# Sheet1.net
KiCad netlist of a schematic drawn in Altium Designer
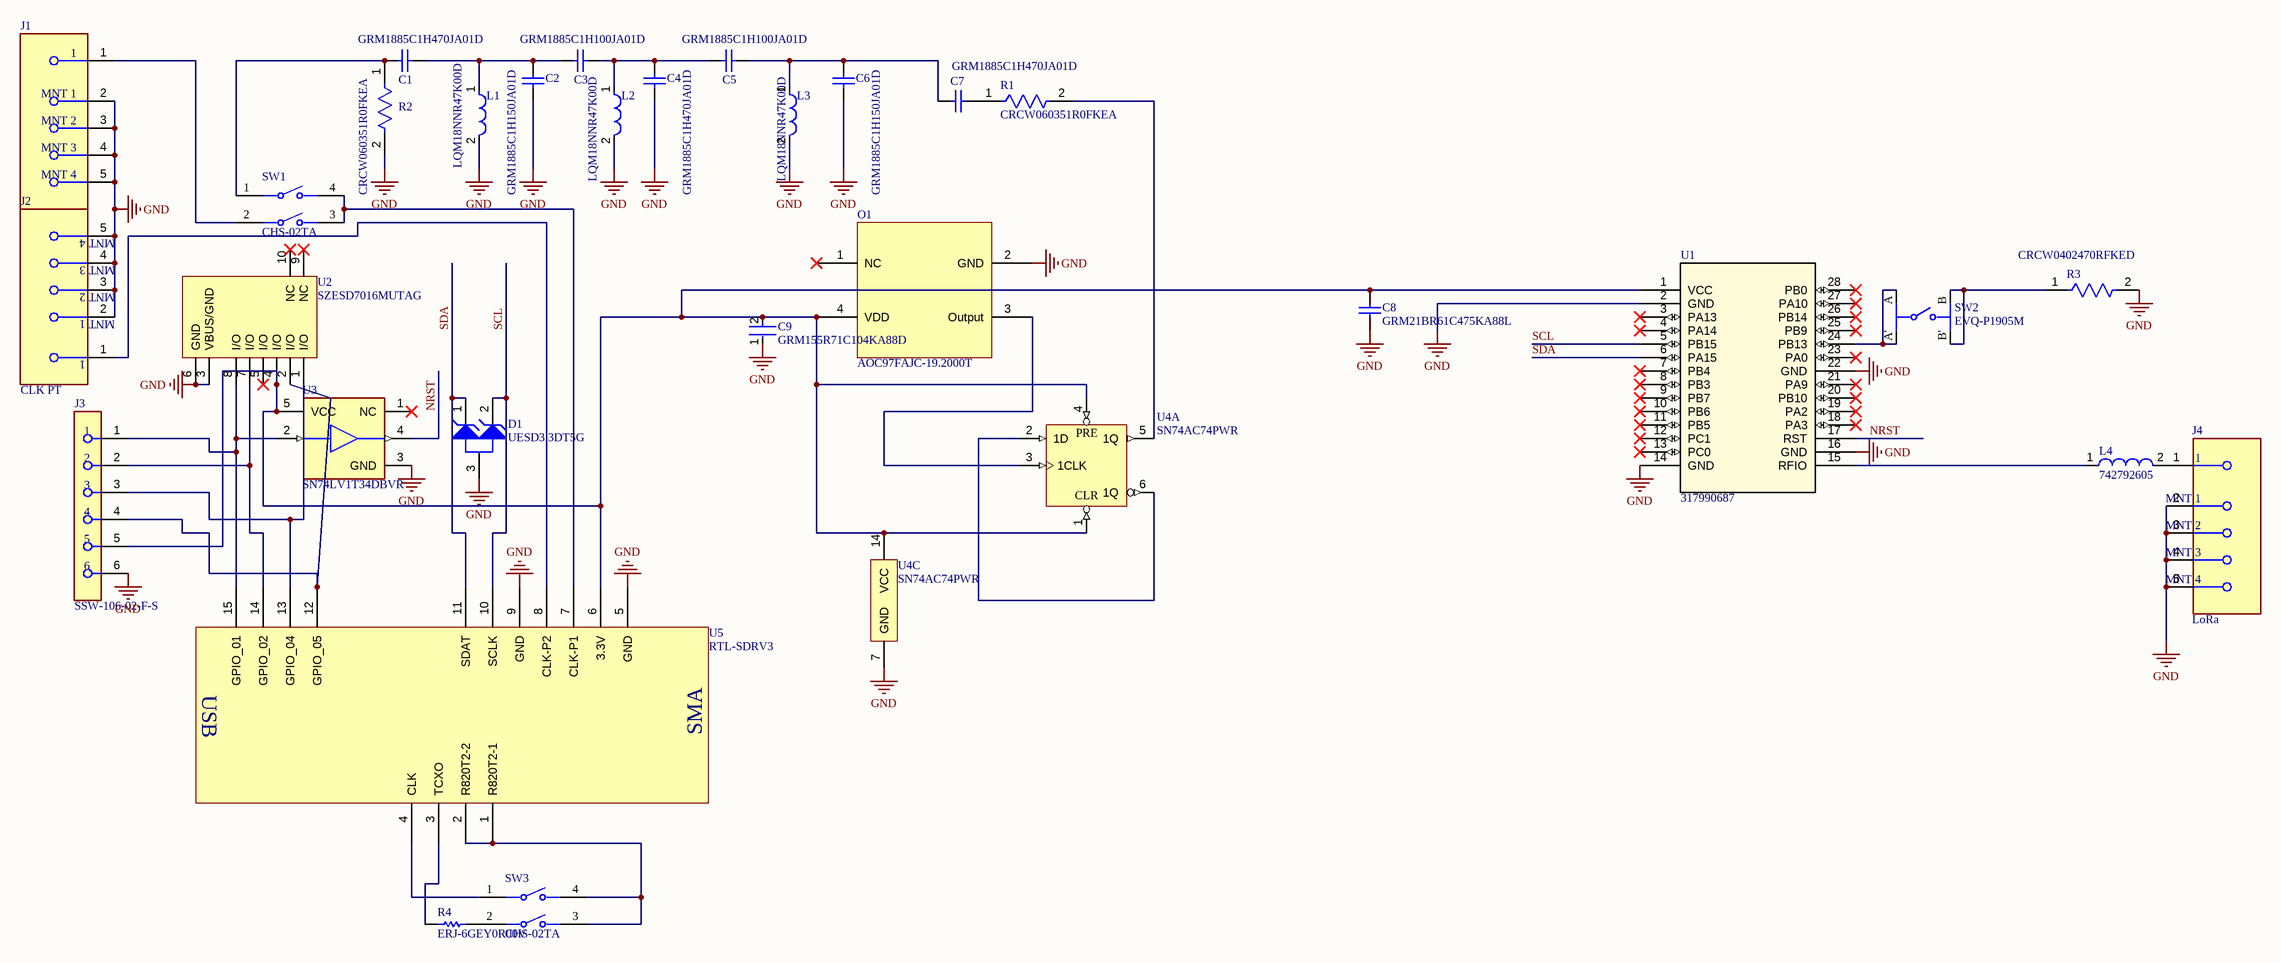
[diagram p0: Sheet1.SchDoc]

(export (version "E")
  (design (tool "Eeschema 10.0.6"))
  (components
    (comp (ref "C1")
      (value "GRM1885C1H470JA01D")
      (footprint "CAPC1608X90X35ML10T15")
      (fields (field (name "MANUFACTURER") "Murata"))
      (libsource (lib "Altium Content Vault") (part "CAP"))
    )
    (comp (ref "C2")
      (value "GRM1885C1H150JA01D")
      (footprint "CAPC1608X90X35ML10T15")
      (fields (field (name "MANUFACTURER") "Murata"))
      (libsource (lib "Altium Content Vault") (part "CAP"))
    )
    (comp (ref "C3")
      (value "GRM1885C1H100JA01D")
      (footprint "CAPC1608X90X35LL10T15")
      (fields (field (name "MANUFACTURER") "Murata"))
      (libsource (lib "Altium Content Vault") (part "CAP"))
    )
    (comp (ref "C4")
      (value "GRM1885C1H470JA01D")
      (footprint "CAPC1608X90X35ML10T15")
      (fields (field (name "MANUFACTURER") "Murata"))
      (libsource (lib "Altium Content Vault") (part "CAP"))
    )
    (comp (ref "C5")
      (value "GRM1885C1H100JA01D")
      (footprint "CAPC1608X90X35LL10T15")
      (fields (field (name "MANUFACTURER") "Murata"))
      (libsource (lib "Altium Content Vault") (part "CAP"))
    )
    (comp (ref "C6")
      (value "GRM1885C1H150JA01D")
      (footprint "CAPC1608X90X35ML10T15")
      (fields (field (name "MANUFACTURER") "Murata"))
      (libsource (lib "Altium Content Vault") (part "CAP"))
    )
    (comp (ref "C7")
      (value "GRM1885C1H470JA01D")
      (footprint "CAPC1608X90X35ML10T15")
      (fields (field (name "MANUFACTURER") "Murata"))
      (libsource (lib "Altium Content Vault") (part "CAP"))
    )
    (comp (ref "C8")
      (value "GRM21BR61C475KA88L")
      (footprint "CAPC2013X135X45LL10T25")
      (description "Chip Capacitor, 4.7 uF, +/- 10%, 16 V, -55 to 85 degC, 0805 (2012 Metric), RoHS, Tape and Reel")
      (fields (field (name "TOLERANCE") "10%"))
      (libsource (lib "Altium Content Vault") (part "CAP-NP-2"))
    )
    (comp (ref "C9")
      (value "GRM155R71C104KA88D")
      (footprint "FP-GRM15-MFG")
      (description "CAP CER 0.1UF 16V X7R 0402")
      (fields
        (field (name "TOLERANCE") "10%")
        (field (name "OCTOPART") "https://octopart.com/grm155r71c104ka88d-murata-196880")
      )
      (libsource (lib "Altium Content Vault") (part "236180d848d6139a670b325ea6854c9"))
    )
    (comp (ref "D1")
      (value "UESD3.3DT5G")
      (footprint "ONSC-SOT-723-3-631AA-01_V")
      (description "ESD Protection Diode, 3-Pin SOT-723, Pb-Free, Tape and Reel")
      (fields (field (name "MANUFACTURER") "On Semiconductor"))
      (libsource (lib "Altium Content Vault") (part "ONSC-K1K2A3-3"))
    )
    (comp (ref "J1")
      (value "CLK IO")
      (footprint "FP-73391-0083-MFG")
      (description "SMA RA JACK, PCB")
      (libsource (lib "") (part "c65b8a639cdaef1819ea20b5466f8fa_2"))
    )
    (comp (ref "J2")
      (value "CLK PT")
      (footprint "FP-73391-0083-MFG")
      (description "SMA RA JACK, PCB")
      (libsource (lib "") (part "c65b8a639cdaef1819ea20b5466f8fa_1"))
    )
    (comp (ref "J3")
      (value "SSW-106-02-F-S")
      (footprint "FP-SSW-106-02-F-S-MFG")
      (description "CONN RCPT 6POS 0.1 GOLD PCB")
      (libsource (lib "Altium Content Vault") (part "340f86754993f25901839ab6d466df7"))
    )
    (comp (ref "J4")
      (value "LoRa")
      (footprint "FP-73391-0083-MFG")
      (description "SMA RA JACK, PCB")
      (libsource (lib "Altium Content Vault") (part "c65b8a639cdaef1819ea20b5466f8fa"))
    )
    (comp (ref "L1")
      (value "LQM18NNR47K00D")
      (footprint "FP-LQM18NN_00-IPC_A")
      (description "Multilayer Type Inductor for General Circuits, 0603 (1608), 470nH, 10%, 1.35Ω, 35mA")
      (fields (field (name "TOLERANCE") "10%"))
      (libsource (lib "Altium Content Vault") (part "725321dda6339637d4d059423bc1c3c"))
    )
    (comp (ref "L2")
      (value "LQM18NNR47K00D")
      (footprint "FP-LQM18NN_00-IPC_A")
      (description "Multilayer Type Inductor for General Circuits, 0603 (1608), 470nH, 10%, 1.35Ω, 35mA")
      (fields (field (name "TOLERANCE") "10%"))
      (libsource (lib "Altium Content Vault") (part "725321dda6339637d4d059423bc1c3c"))
    )
    (comp (ref "L3")
      (value "LQM18NNR47K00D")
      (footprint "FP-LQM18NN_00-IPC_A")
      (description "Multilayer Type Inductor for General Circuits, 0603 (1608), 470nH, 10%, 1.35Ω, 35mA")
      (fields (field (name "TOLERANCE") "10%"))
      (libsource (lib "Altium Content Vault") (part "725321dda6339637d4d059423bc1c3c"))
    )
    (comp (ref "L4")
      (value "742792605")
      (footprint "SMD-0603")
      (description "SMD EMI Suppression Ferrite Bead WE-CBF, Z = 33 Ohm")
      (libsource (lib "Altium Content Vault") (part "PAS-IND-INDUCTOR-2"))
    )
    (comp (ref "O1")
      (value "AOC97FAJC-19.2000T")
      (footprint "AOC97FAJC-19.2000T")
      (libsource (lib "RTLSDRV3") (part "AOC97FAJC-19.2000T"))
    )
    (comp (ref "R1")
      (value "CRCW060351R0FKEA")
      (footprint "FP-CRCW0603-e3-MFG")
      (description "RES Thick Film, 51Ω, 1%, 0.1W, 100ppm/°C, 0603")
      (fields (field (name "TOLERANCE") "1%"))
      (libsource (lib "Altium Content Vault") (part "1029c3af85768c4190bb7ad29bc67b5"))
    )
    (comp (ref "R2")
      (value "CRCW060351R0FKEA")
      (footprint "FP-CRCW0603-e3-MFG")
      (description "RES Thick Film, 51Ω, 1%, 0.1W, 100ppm/°C, 0603")
      (fields (field (name "TOLERANCE") "1%"))
      (libsource (lib "Altium Content Vault") (part "1029c3af85768c4190bb7ad29bc67b5"))
    )
    (comp (ref "R3")
      (value "CRCW0402470RFKED")
      (footprint "FP-CRCW0402-e3-MFG")
      (description "RES Thick Film, 470Ω, 1%, 0.063W, 100ppm/°C, 0402")
      (fields (field (name "TOLERANCE") "1%"))
      (libsource (lib "Altium Content Vault") (part "1029c3af85768c4190bb7ad29bc67b5"))
    )
    (comp (ref "R4")
      (value "ERJ-6GEY0R00V")
      (footprint "RESC2013X70X40NL20T20")
      (description "Chip Resistor, 0 Ohm, +/- 1%, 0.125 W, -55 to 155 degC, 0805 (2012 Metric), RoHS, Tape and Reel")
      (fields (field (name "TOLERANCE") "5%"))
      (libsource (lib "Altium Content Vault") (part "RES-2"))
    )
    (comp (ref "SW1")
      (value "CHS-02TA")
      (footprint "FP-CHS-02TA-MFG")
      (description "SWITCH SLIDE DIP SPST 100MA 6V")
      (libsource (lib "Altium Content Vault") (part "69afdd861a03aec749b083f1f974c11"))
    )
    (comp (ref "SW2")
      (value "EVQ-P1905M")
      (footprint "FP-EVQ-P1905M-MFG")
      (description "SWITCH TACTILE SPST-NO 0.05A 12V")
      (libsource (lib "Altium Content Vault") (part "75038bc65b1af1a6bd057da08483287"))
    )
    (comp (ref "SW3")
      (value "CHS-02TA")
      (footprint "FP-CHS-02TA-MFG")
      (description "SWITCH SLIDE DIP SPST 100MA 6V")
      (libsource (lib "Altium Content Vault") (part "69afdd861a03aec749b083f1f974c11"))
    )
    (comp (ref "U1")
      (value "317990687")
      (footprint "QFN_90687_SEE")
      (description "No Description Available")
      (fields (field (name "COPYRIGHT") "Copyright (C) 2025 Ultra Librarian. All rights reserved."))
      (libsource (lib "317990687") (part "317990687"))
    )
    (comp (ref "U2")
      (value "SZESD7016MUTAG")
      (footprint "ONSC-UDFN-8-517CB_V")
      (description "Low Capacitance ESD Protection USB3.0, 8-Pin UDFN, Pb-Free, Tape and Reel")
      (fields (field (name "MANUFACTURER") "On Semiconductor"))
      (libsource (lib "Altium Content Vault") (part "ONSC-ESD7016-UDFN-8-517CB"))
    )
    (comp (ref "U3")
      (value "SN74LV1T34DBVR")
      (footprint "FP-DBV0005A-IPC_B")
      (description "IC BUF NON-INVERT 5.5V SOT23-5")
      (libsource (lib "Altium Content Vault") (part "d03805866fcc65e5014dff611fc4129"))
    )
    (comp (ref "U4")
      (value "SN74AC74PWR")
      (footprint "PW0014A_L")
      (description "Dual Positive-Edge-Triggered D-Type Flip-Flops With Clear and Preset, PW0014A, LARGE T&R")
      (fields
        (field (name "GENERIC PART NUMBER") "SN74AC74")
        (field (name "MANUFACTURER") "Texas Instruments")
      )
      (libsource (lib "Altium Content Vault") (part "TI-CD_SNX4XXXX74X-14"))
    )
    (comp (ref "U5")
      (value "RTL-SDRV3")
      (footprint "RTLSDR V3")
      (libsource (lib "RTLSDRV3") (part "RTL-SDR"))
    )
  )
  (nets
    (net (code "1") (name "/NRST") (class "Default")
      (node (ref "U1") (pin "17") (pinfunction "RST_17") (pintype "passive"))
      (node (ref "U3") (pin "4") (pinfunction "Y_4") (pintype "output"))
    )
    (net (code "2") (name "/SCL") (class "Default")
      (node (ref "D1") (pin "2") (pinfunction "K2_2") (pintype "passive"))
      (node (ref "U1") (pin "5") (pinfunction "PB15_5") (pintype "bidirectional"))
      (node (ref "U5") (pin "10") (pinfunction "SCLK_10") (pintype "passive"))
    )
    (net (code "3") (name "/SDA") (class "Default")
      (node (ref "D1") (pin "1") (pinfunction "K1_1") (pintype "passive"))
      (node (ref "U1") (pin "6") (pinfunction "PA15_6") (pintype "bidirectional"))
      (node (ref "U5") (pin "11") (pinfunction "SDAT_11") (pintype "passive"))
    )
    (net (code "4") (name "GND") (class "Default")
      (node (ref "C2") (pin "1") (pinfunction "1_1") (pintype "passive"))
      (node (ref "C4") (pin "1") (pinfunction "1_1") (pintype "passive"))
      (node (ref "C6") (pin "1") (pinfunction "1_1") (pintype "passive"))
      (node (ref "C8") (pin "1") (pinfunction "1_1") (pintype "passive"))
      (node (ref "C9") (pin "1") (pinfunction "1_1") (pintype "passive"))
      (node (ref "D1") (pin "3") (pinfunction "A_3") (pintype "passive"))
      (node (ref "J1") (pin "2") (pinfunction "MNT_1_2") (pintype "passive"))
      (node (ref "J1") (pin "3") (pinfunction "MNT_2_3") (pintype "passive"))
      (node (ref "J1") (pin "4") (pinfunction "MNT_3_4") (pintype "passive"))
      (node (ref "J1") (pin "5") (pinfunction "MNT_4_5") (pintype "passive"))
      (node (ref "J2") (pin "2") (pinfunction "MNT_1_2") (pintype "passive"))
      (node (ref "J2") (pin "3") (pinfunction "MNT_2_3") (pintype "passive"))
      (node (ref "J2") (pin "4") (pinfunction "MNT_3_4") (pintype "passive"))
      (node (ref "J2") (pin "5") (pinfunction "MNT_4_5") (pintype "passive"))
      (node (ref "J3") (pin "6") (pinfunction "6_6") (pintype "passive"))
      (node (ref "J4") (pin "2") (pinfunction "MNT_1_2") (pintype "passive"))
      (node (ref "J4") (pin "3") (pinfunction "MNT_2_3") (pintype "passive"))
      (node (ref "J4") (pin "4") (pinfunction "MNT_3_4") (pintype "passive"))
      (node (ref "J4") (pin "5") (pinfunction "MNT_4_5") (pintype "passive"))
      (node (ref "L1") (pin "2") (pinfunction "2_2") (pintype "passive"))
      (node (ref "L2") (pin "2") (pinfunction "2_2") (pintype "passive"))
      (node (ref "L3") (pin "2") (pinfunction "2_2") (pintype "passive"))
      (node (ref "O1") (pin "2") (pinfunction "GND_2") (pintype "passive"))
      (node (ref "R2") (pin "2") (pinfunction "2_2") (pintype "passive"))
      (node (ref "R3") (pin "2") (pinfunction "2_2") (pintype "passive"))
      (node (ref "U1") (pin "14") (pinfunction "GND_14") (pintype "power_in"))
      (node (ref "U1") (pin "16") (pinfunction "GND_16") (pintype "power_in"))
      (node (ref "U1") (pin "2") (pinfunction "GND_2") (pintype "power_in"))
      (node (ref "U1") (pin "22") (pinfunction "GND_22") (pintype "power_in"))
      (node (ref "U2") (pin "3") (pinfunction "VBUS/GND_3") (pintype "power_in"))
      (node (ref "U2") (pin "6") (pinfunction "GND_6") (pintype "power_in"))
      (node (ref "U3") (pin "3") (pinfunction "GND_3") (pintype "power_in"))
      (node (ref "U4") (pin "7") (pinfunction "GND_7") (pintype "power_in"))
      (node (ref "U5") (pin "5") (pinfunction "GND_5") (pintype "passive"))
      (node (ref "U5") (pin "9") (pinfunction "GND_9") (pintype "passive"))
    )
    (net (code "5") (name "Net-(C1-Pad1)") (class "Default")
      (node (ref "C1") (pin "1") (pinfunction "1_1") (pintype "passive"))
      (node (ref "C2") (pin "2") (pinfunction "2_2") (pintype "passive"))
      (node (ref "C3") (pin "1") (pinfunction "1_1") (pintype "passive"))
      (node (ref "L1") (pin "1") (pinfunction "1_1") (pintype "passive"))
    )
    (net (code "6") (name "Net-(C1-Pad2)") (class "Default")
      (node (ref "C1") (pin "2") (pinfunction "2_2") (pintype "passive"))
      (node (ref "R2") (pin "1") (pinfunction "1_1") (pintype "passive"))
      (node (ref "SW1") (pin "1") (pinfunction "1_1") (pintype "passive"))
    )
    (net (code "7") (name "Net-(C3-Pad2)") (class "Default")
      (node (ref "C3") (pin "2") (pinfunction "2_2") (pintype "passive"))
      (node (ref "C4") (pin "2") (pinfunction "2_2") (pintype "passive"))
      (node (ref "C5") (pin "1") (pinfunction "1_1") (pintype "passive"))
      (node (ref "L2") (pin "1") (pinfunction "1_1") (pintype "passive"))
    )
    (net (code "8") (name "Net-(C5-Pad2)") (class "Default")
      (node (ref "C5") (pin "2") (pinfunction "2_2") (pintype "passive"))
      (node (ref "C6") (pin "2") (pinfunction "2_2") (pintype "passive"))
      (node (ref "C7") (pin "1") (pinfunction "1_1") (pintype "passive"))
      (node (ref "L3") (pin "1") (pinfunction "1_1") (pintype "passive"))
    )
    (net (code "9") (name "Net-(C7-Pad2)") (class "Default")
      (node (ref "C7") (pin "2") (pinfunction "2_2") (pintype "passive"))
      (node (ref "R1") (pin "1") (pinfunction "1_1") (pintype "passive"))
    )
    (net (code "10") (name "Net-(J1-Pad1)") (class "Default")
      (node (ref "J1") (pin "1") (pinfunction "1_1") (pintype "passive"))
      (node (ref "SW1") (pin "2") (pinfunction "2_2") (pintype "passive"))
    )
    (net (code "11") (name "Net-(J4-Pad1)") (class "Default")
      (node (ref "J4") (pin "1") (pinfunction "1_1") (pintype "passive"))
      (node (ref "L4") (pin "2") (pinfunction "2_2") (pintype "passive"))
    )
    (net (code "12") (name "Net-(O1-Output)") (class "Default")
      (node (ref "O1") (pin "3") (pinfunction "Output_3") (pintype "passive"))
      (node (ref "U4") (pin "3") (pinfunction "1CLK_3") (pintype "input"))
    )
    (net (code "13") (name "Net-(O1-VDD)") (class "Default")
      (node (ref "C8") (pin "2") (pinfunction "2_2") (pintype "passive"))
      (node (ref "C9") (pin "2") (pinfunction "2_2") (pintype "passive"))
      (node (ref "J3") (pin "5") (pinfunction "5_5") (pintype "passive"))
      (node (ref "O1") (pin "4") (pinfunction "VDD_4") (pintype "passive"))
      (node (ref "U1") (pin "1") (pinfunction "VCC_1") (pintype "power_in"))
      (node (ref "U2") (pin "4") (pinfunction "I/O_4") (pintype "passive"))
      (node (ref "U3") (pin "5") (pinfunction "VCC_5") (pintype "power_in"))
      (node (ref "U4") (pin "1") (pinfunction "1~{CLR}_1") (pintype "input"))
      (node (ref "U4") (pin "14") (pinfunction "VCC_14") (pintype "power_in"))
      (node (ref "U4") (pin "4") (pinfunction "1~{PRE}_4") (pintype "input"))
      (node (ref "U5") (pin "6") (pinfunction "3.3V_6") (pintype "passive"))
    )
    (net (code "14") (name "Net-(R1-Pad2)") (class "Default")
      (node (ref "R1") (pin "2") (pinfunction "2_2") (pintype "passive"))
      (node (ref "U4") (pin "5") (pinfunction "1Q_5") (pintype "output"))
    )
    (net (code "15") (name "Net-(R3-Pad1)") (class "Default")
      (node (ref "R3") (pin "1") (pinfunction "1_1") (pintype "passive"))
      (node (ref "SW2") (pin "B") (pinfunction "B_B") (pintype "passive"))
      (node (ref "SW2") (pin "B'") (pinfunction "B'_B'") (pintype "passive"))
    )
    (net (code "16") (name "Net-(R4-Pad2)") (class "Default")
      (node (ref "R4") (pin "2") (pinfunction "2_2") (pintype "passive"))
      (node (ref "SW3") (pin "2") (pinfunction "2_2") (pintype "passive"))
    )
    (net (code "17") (name "Net-(U1-PB13)") (class "Default")
      (node (ref "SW2") (pin "A") (pinfunction "A_A") (pintype "passive"))
      (node (ref "SW2") (pin "A'") (pinfunction "A'_A'") (pintype "passive"))
      (node (ref "U1") (pin "24") (pinfunction "PB13_24") (pintype "bidirectional"))
    )
    (net (code "18") (name "Net-(U1-RFIO)") (class "Default")
      (node (ref "L4") (pin "1") (pinfunction "1_1") (pintype "passive"))
      (node (ref "U1") (pin "15") (pinfunction "RFIO_15") (pintype "passive"))
    )
    (net (code "19") (name "Net-(U3-A)") (class "Default")
      (node (ref "J3") (pin "1") (pinfunction "1_1") (pintype "passive"))
      (node (ref "U2") (pin "8") (pinfunction "I/O_8") (pintype "passive"))
      (node (ref "U3") (pin "2") (pinfunction "A_2") (pintype "input"))
      (node (ref "U5") (pin "15") (pinfunction "GPIO_01_15") (pintype "passive"))
    )
    (net (code "20") (name "Net-(U4A-1D)") (class "Default")
      (node (ref "U4") (pin "2") (pinfunction "1D_2") (pintype "input"))
      (node (ref "U4") (pin "6") (pinfunction "1Q_6") (pintype "output"))
    )
    (net (code "21") (name "Net-(U5-CLK)") (class "Default")
      (node (ref "SW3") (pin "1") (pinfunction "1_1") (pintype "passive"))
      (node (ref "U5") (pin "4") (pinfunction "CLK_4") (pintype "passive"))
    )
    (net (code "22") (name "Net-(U5-CLK-P1)") (class "Default")
      (node (ref "SW1") (pin "3") (pinfunction "3_3") (pintype "passive"))
      (node (ref "SW1") (pin "4") (pinfunction "4_4") (pintype "passive"))
      (node (ref "U5") (pin "7") (pinfunction "CLK-P1_7") (pintype "passive"))
    )
    (net (code "23") (name "Net-(U5-CLK-P2)") (class "Default")
      (node (ref "J2") (pin "1") (pinfunction "1_1") (pintype "passive"))
      (node (ref "U5") (pin "8") (pinfunction "CLK-P2_8") (pintype "passive"))
    )
    (net (code "24") (name "Net-(U5-GPIO_02)") (class "Default")
      (node (ref "J3") (pin "2") (pinfunction "2_2") (pintype "passive"))
      (node (ref "U2") (pin "7") (pinfunction "I/O_7") (pintype "passive"))
      (node (ref "U5") (pin "14") (pinfunction "GPIO_02_14") (pintype "passive"))
    )
    (net (code "25") (name "Net-(U5-GPIO_04)") (class "Default")
      (node (ref "J3") (pin "3") (pinfunction "3_3") (pintype "passive"))
      (node (ref "U2") (pin "1") (pinfunction "I/O_1") (pintype "passive"))
      (node (ref "U5") (pin "13") (pinfunction "GPIO_04_13") (pintype "passive"))
    )
    (net (code "26") (name "Net-(U5-GPIO_05)") (class "Default")
      (node (ref "J3") (pin "4") (pinfunction "4_4") (pintype "passive"))
      (node (ref "U2") (pin "2") (pinfunction "I/O_2") (pintype "passive"))
      (node (ref "U5") (pin "12") (pinfunction "GPIO_05_12") (pintype "passive"))
    )
    (net (code "27") (name "Net-(U5-R820T2-1)") (class "Default")
      (node (ref "SW3") (pin "3") (pinfunction "3_3") (pintype "passive"))
      (node (ref "SW3") (pin "4") (pinfunction "4_4") (pintype "passive"))
      (node (ref "U5") (pin "1") (pinfunction "R820T2-1_1") (pintype "passive"))
      (node (ref "U5") (pin "2") (pinfunction "R820T2-2_2") (pintype "passive"))
    )
    (net (code "28") (name "Net-(U5-TCXO)") (class "Default")
      (node (ref "R4") (pin "1") (pinfunction "1_1") (pintype "passive"))
      (node (ref "U5") (pin "3") (pinfunction "TCXO_3") (pintype "passive"))
    )
    (net (code "29") (name "unconnected-(O1-NC-Pad1)") (class "Default")
      (node (ref "O1") (pin "1") (pinfunction "NC_1") (pintype "passive+no_connect"))
    )
    (net (code "30") (name "unconnected-(U1-PA0-Pad23)") (class "Default")
      (node (ref "U1") (pin "23") (pinfunction "PA0_23") (pintype "bidirectional+no_connect"))
    )
    (net (code "31") (name "unconnected-(U1-PA2-Pad19)") (class "Default")
      (node (ref "U1") (pin "19") (pinfunction "PA2_19") (pintype "bidirectional+no_connect"))
    )
    (net (code "32") (name "unconnected-(U1-PA3-Pad18)") (class "Default")
      (node (ref "U1") (pin "18") (pinfunction "PA3_18") (pintype "bidirectional+no_connect"))
    )
    (net (code "33") (name "unconnected-(U1-PA9-Pad21)") (class "Default")
      (node (ref "U1") (pin "21") (pinfunction "PA9_21") (pintype "bidirectional+no_connect"))
    )
    (net (code "34") (name "unconnected-(U1-PA10-Pad27)") (class "Default")
      (node (ref "U1") (pin "27") (pinfunction "PA10_27") (pintype "bidirectional+no_connect"))
    )
    (net (code "35") (name "unconnected-(U1-PA13-Pad3)") (class "Default")
      (node (ref "U1") (pin "3") (pinfunction "PA13_3") (pintype "bidirectional+no_connect"))
    )
    (net (code "36") (name "unconnected-(U1-PA14-Pad4)") (class "Default")
      (node (ref "U1") (pin "4") (pinfunction "PA14_4") (pintype "bidirectional+no_connect"))
    )
    (net (code "37") (name "unconnected-(U1-PB0-Pad28)") (class "Default")
      (node (ref "U1") (pin "28") (pinfunction "PB0_28") (pintype "bidirectional+no_connect"))
    )
    (net (code "38") (name "unconnected-(U1-PB3-Pad8)") (class "Default")
      (node (ref "U1") (pin "8") (pinfunction "PB3_8") (pintype "bidirectional+no_connect"))
    )
    (net (code "39") (name "unconnected-(U1-PB4-Pad7)") (class "Default")
      (node (ref "U1") (pin "7") (pinfunction "PB4_7") (pintype "bidirectional+no_connect"))
    )
    (net (code "40") (name "unconnected-(U1-PB5-Pad11)") (class "Default")
      (node (ref "U1") (pin "11") (pinfunction "PB5_11") (pintype "bidirectional+no_connect"))
    )
    (net (code "41") (name "unconnected-(U1-PB6-Pad10)") (class "Default")
      (node (ref "U1") (pin "10") (pinfunction "PB6_10") (pintype "bidirectional+no_connect"))
    )
    (net (code "42") (name "unconnected-(U1-PB7-Pad9)") (class "Default")
      (node (ref "U1") (pin "9") (pinfunction "PB7_9") (pintype "bidirectional+no_connect"))
    )
    (net (code "43") (name "unconnected-(U1-PB9-Pad25)") (class "Default")
      (node (ref "U1") (pin "25") (pinfunction "PB9_25") (pintype "bidirectional+no_connect"))
    )
    (net (code "44") (name "unconnected-(U1-PB10-Pad20)") (class "Default")
      (node (ref "U1") (pin "20") (pinfunction "PB10_20") (pintype "bidirectional+no_connect"))
    )
    (net (code "45") (name "unconnected-(U1-PB14-Pad26)") (class "Default")
      (node (ref "U1") (pin "26") (pinfunction "PB14_26") (pintype "bidirectional+no_connect"))
    )
    (net (code "46") (name "unconnected-(U1-PC0-Pad13)") (class "Default")
      (node (ref "U1") (pin "13") (pinfunction "PC0_13") (pintype "bidirectional+no_connect"))
    )
    (net (code "47") (name "unconnected-(U1-PC1-Pad12)") (class "Default")
      (node (ref "U1") (pin "12") (pinfunction "PC1_12") (pintype "bidirectional+no_connect"))
    )
    (net (code "48") (name "unconnected-(U2-I{slash}O-Pad5)") (class "Default")
      (node (ref "U2") (pin "5") (pinfunction "I/O_5") (pintype "passive+no_connect"))
    )
    (net (code "49") (name "unconnected-(U2-NC-Pad9)") (class "Default")
      (node (ref "U2") (pin "9") (pinfunction "NC_9") (pintype "passive+no_connect"))
    )
    (net (code "50") (name "unconnected-(U2-NC-Pad10)") (class "Default")
      (node (ref "U2") (pin "10") (pinfunction "NC_10") (pintype "passive+no_connect"))
    )
    (net (code "51") (name "unconnected-(U3-NC-Pad1)") (class "Default")
      (node (ref "U3") (pin "1") (pinfunction "NC_1") (pintype "passive+no_connect"))
    )
  )
)
